# Sensors.net
KiCad netlist of a schematic drawn in Altium Designer
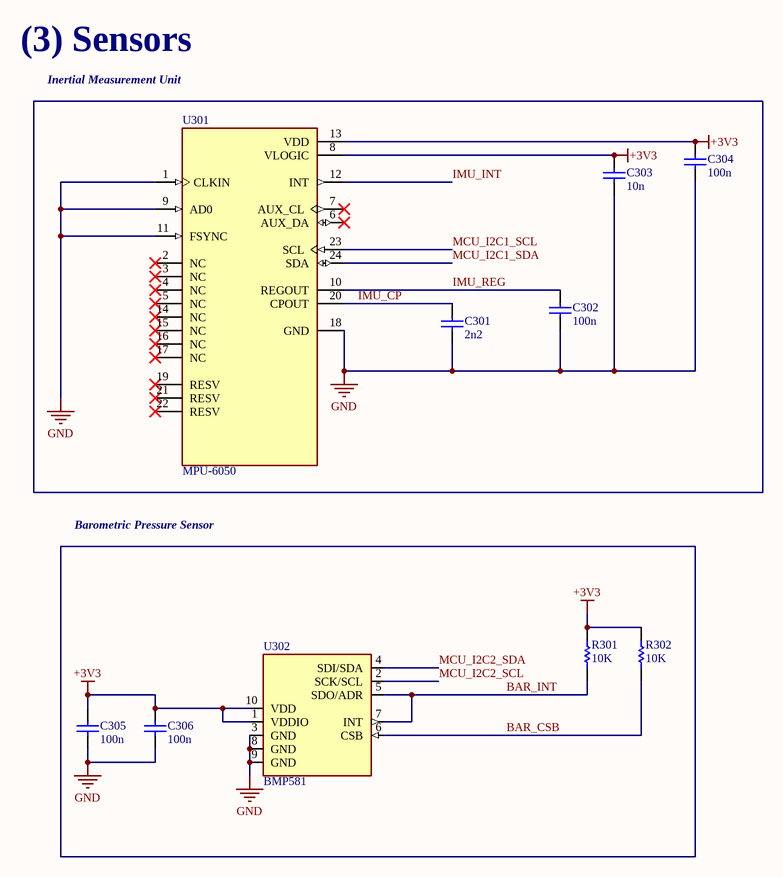
[diagram p0: Sensors.SchDoc]

(export (version "E")
  (design (tool "Eeschema 10.0.6"))
  (components
    (comp (ref "C301")
      (value "2n2")
      (footprint "CAP-SM-0805")
      (description "Capacitor")
      (fields (field (name "Comment") "Cap Non-Pol SMD"))
      (libsource (lib "PIF_Library") (part "Cap Non-Pol SMD"))
    )
    (comp (ref "C302")
      (value "100n")
      (footprint "CAP-SM-0805")
      (description "Capacitor")
      (fields (field (name "Comment") "Cap Non-Pol SMD"))
      (libsource (lib "PIF_Library") (part "Cap Non-Pol SMD"))
    )
    (comp (ref "C303")
      (value "10n")
      (footprint "CAP-SM-0805")
      (description "Capacitor")
      (fields (field (name "Comment") "Cap Non-Pol SMD"))
      (libsource (lib "PIF_Library") (part "Cap Non-Pol SMD"))
    )
    (comp (ref "C304")
      (value "100n")
      (footprint "CAP-SM-0805")
      (description "Capacitor")
      (fields (field (name "Comment") "Cap Non-Pol SMD"))
      (libsource (lib "PIF_Library") (part "Cap Non-Pol SMD"))
    )
    (comp (ref "C305")
      (value "100n")
      (footprint "CAP-SM-0805")
      (description "Capacitor")
      (fields (field (name "Comment") "Cap Non-Pol SMD"))
      (libsource (lib "PIF_Library") (part "Cap Non-Pol SMD"))
    )
    (comp (ref "C306")
      (value "100n")
      (footprint "CAP-SM-0805")
      (description "Capacitor")
      (fields (field (name "Comment") "Cap Non-Pol SMD"))
      (libsource (lib "PIF_Library") (part "Cap Non-Pol SMD"))
    )
    (comp (ref "R301")
      (value "10K")
      (footprint "RES-SM-0603")
      (description "Resistor")
      (fields (field (name "Comment") "RESISTOR SMD"))
      (libsource (lib "PIF_Library") (part "RESISTOR SMD"))
    )
    (comp (ref "R302")
      (value "10K")
      (footprint "RES-SM-0603")
      (description "Resistor")
      (fields (field (name "Comment") "RESISTOR SMD"))
      (libsource (lib "PIF_Library") (part "RESISTOR SMD"))
    )
    (comp (ref "U301")
      (value "MPU-6050")
      (footprint "QFN50P400X400X95-24N")
      (description "MPU-6050 series Accelerometer, Gyroscope, 3 Axis Sensor Evaluation Board")
      (fields (field (name "MF") "TDK InvenSense"))
      (libsource (lib "MPU-6050") (part "MPU-6050"))
    )
    (comp (ref "U302")
      (value "BMP581")
      (footprint "BMP581")
      (fields (field (name "MF") "Bosch"))
      (libsource (lib "BMP581") (part "BMP581"))
    )
  )
  (nets
    (net (code "1") (name "+3V3") (class "Default")
      (node (ref "C303") (pin "2") (pinfunction "2_2") (pintype "passive"))
      (node (ref "C304") (pin "1") (pinfunction "1_1") (pintype "passive"))
      (node (ref "C305") (pin "2") (pinfunction "2_2") (pintype "passive"))
      (node (ref "C306") (pin "2") (pinfunction "2_2") (pintype "passive"))
      (node (ref "R301") (pin "2") (pinfunction "2_2") (pintype "passive"))
      (node (ref "R302") (pin "2") (pinfunction "2_2") (pintype "passive"))
      (node (ref "U301") (pin "13") (pinfunction "VDD_13") (pintype "power_in"))
      (node (ref "U301") (pin "8") (pinfunction "VLOGIC_8") (pintype "power_in"))
      (node (ref "U302") (pin "1") (pinfunction "VDDIO_1") (pintype "power_in"))
      (node (ref "U302") (pin "10") (pinfunction "VDD_10") (pintype "power_in"))
    )
    (net (code "2") (name "/BAR_CSB") (class "Default")
      (node (ref "R302") (pin "1") (pinfunction "1_1") (pintype "passive"))
      (node (ref "U302") (pin "6") (pinfunction "CSB_6") (pintype "input"))
    )
    (net (code "3") (name "/BAR_INT") (class "Default")
      (node (ref "R301") (pin "1") (pinfunction "1_1") (pintype "passive"))
      (node (ref "U302") (pin "5") (pinfunction "SDO/ADR_5") (pintype "bidirectional"))
      (node (ref "U302") (pin "7") (pinfunction "INT_7") (pintype "output"))
    )
    (net (code "4") (name "/IMU_CP") (class "Default")
      (node (ref "C301") (pin "2") (pinfunction "2_2") (pintype "passive"))
      (node (ref "U301") (pin "20") (pinfunction "CPOUT_20") (pintype "passive"))
    )
    (net (code "5") (name "/IMU_INT") (class "Default")
      (node (ref "U301") (pin "12") (pinfunction "INT_12") (pintype "output"))
    )
    (net (code "6") (name "/IMU_REG") (class "Default")
      (node (ref "C302") (pin "2") (pinfunction "2_2") (pintype "passive"))
      (node (ref "U301") (pin "10") (pinfunction "REGOUT_10") (pintype "passive"))
    )
    (net (code "7") (name "/MCU_I2C1_SCL") (class "Default")
      (node (ref "U301") (pin "23") (pinfunction "SCL_23") (pintype "input"))
    )
    (net (code "8") (name "/MCU_I2C1_SDA") (class "Default")
      (node (ref "U301") (pin "24") (pinfunction "SDA_24") (pintype "bidirectional"))
    )
    (net (code "9") (name "/MCU_I2C2_SCL") (class "Default")
      (node (ref "U302") (pin "2") (pinfunction "SCK/SCL_2") (pintype "bidirectional"))
    )
    (net (code "10") (name "/MCU_I2C2_SDA") (class "Default")
      (node (ref "U302") (pin "4") (pinfunction "SDI/SDA_4") (pintype "bidirectional"))
    )
    (net (code "11") (name "GND") (class "Default")
      (node (ref "C301") (pin "1") (pinfunction "1_1") (pintype "passive"))
      (node (ref "C302") (pin "1") (pinfunction "1_1") (pintype "passive"))
      (node (ref "C303") (pin "1") (pinfunction "1_1") (pintype "passive"))
      (node (ref "C304") (pin "2") (pinfunction "2_2") (pintype "passive"))
      (node (ref "C305") (pin "1") (pinfunction "1_1") (pintype "passive"))
      (node (ref "C306") (pin "1") (pinfunction "1_1") (pintype "passive"))
      (node (ref "U301") (pin "1") (pinfunction "CLKIN_1") (pintype "input"))
      (node (ref "U301") (pin "11") (pinfunction "FSYNC_11") (pintype "input"))
      (node (ref "U301") (pin "18") (pinfunction "GND_18") (pintype "power_in"))
      (node (ref "U301") (pin "9") (pinfunction "AD0_9") (pintype "input"))
      (node (ref "U302") (pin "3") (pinfunction "GND_3") (pintype "power_in"))
      (node (ref "U302") (pin "8") (pinfunction "GND_8") (pintype "power_in"))
      (node (ref "U302") (pin "9") (pinfunction "GND_9") (pintype "power_in"))
    )
    (net (code "12") (name "unconnected-(U301-AUX_CL-Pad7)") (class "Default")
      (node (ref "U301") (pin "7") (pinfunction "AUX_CL_7") (pintype "output+no_connect"))
    )
    (net (code "13") (name "unconnected-(U301-AUX_DA-Pad6)") (class "Default")
      (node (ref "U301") (pin "6") (pinfunction "AUX_DA_6") (pintype "bidirectional+no_connect"))
    )
    (net (code "14") (name "unconnected-(U301-NC-Pad2)") (class "Default")
      (node (ref "U301") (pin "2") (pinfunction "NC_2") (pintype "passive+no_connect"))
    )
    (net (code "15") (name "unconnected-(U301-NC-Pad3)") (class "Default")
      (node (ref "U301") (pin "3") (pinfunction "NC_3") (pintype "passive+no_connect"))
    )
    (net (code "16") (name "unconnected-(U301-NC-Pad4)") (class "Default")
      (node (ref "U301") (pin "4") (pinfunction "NC_4") (pintype "passive+no_connect"))
    )
    (net (code "17") (name "unconnected-(U301-NC-Pad5)") (class "Default")
      (node (ref "U301") (pin "5") (pinfunction "NC_5") (pintype "passive+no_connect"))
    )
    (net (code "18") (name "unconnected-(U301-NC-Pad14)") (class "Default")
      (node (ref "U301") (pin "14") (pinfunction "NC_14") (pintype "passive+no_connect"))
    )
    (net (code "19") (name "unconnected-(U301-NC-Pad15)") (class "Default")
      (node (ref "U301") (pin "15") (pinfunction "NC_15") (pintype "passive+no_connect"))
    )
    (net (code "20") (name "unconnected-(U301-NC-Pad16)") (class "Default")
      (node (ref "U301") (pin "16") (pinfunction "NC_16") (pintype "passive+no_connect"))
    )
    (net (code "21") (name "unconnected-(U301-NC-Pad17)") (class "Default")
      (node (ref "U301") (pin "17") (pinfunction "NC_17") (pintype "passive+no_connect"))
    )
    (net (code "22") (name "unconnected-(U301-RESV-Pad19)") (class "Default")
      (node (ref "U301") (pin "19") (pinfunction "RESV_19") (pintype "passive+no_connect"))
    )
    (net (code "23") (name "unconnected-(U301-RESV-Pad21)") (class "Default")
      (node (ref "U301") (pin "21") (pinfunction "RESV_21") (pintype "passive+no_connect"))
    )
    (net (code "24") (name "unconnected-(U301-RESV-Pad22)") (class "Default")
      (node (ref "U301") (pin "22") (pinfunction "RESV_22") (pintype "passive+no_connect"))
    )
  )
)
